# controller.net
KiCad netlist of a schematic drawn in Altium Designer
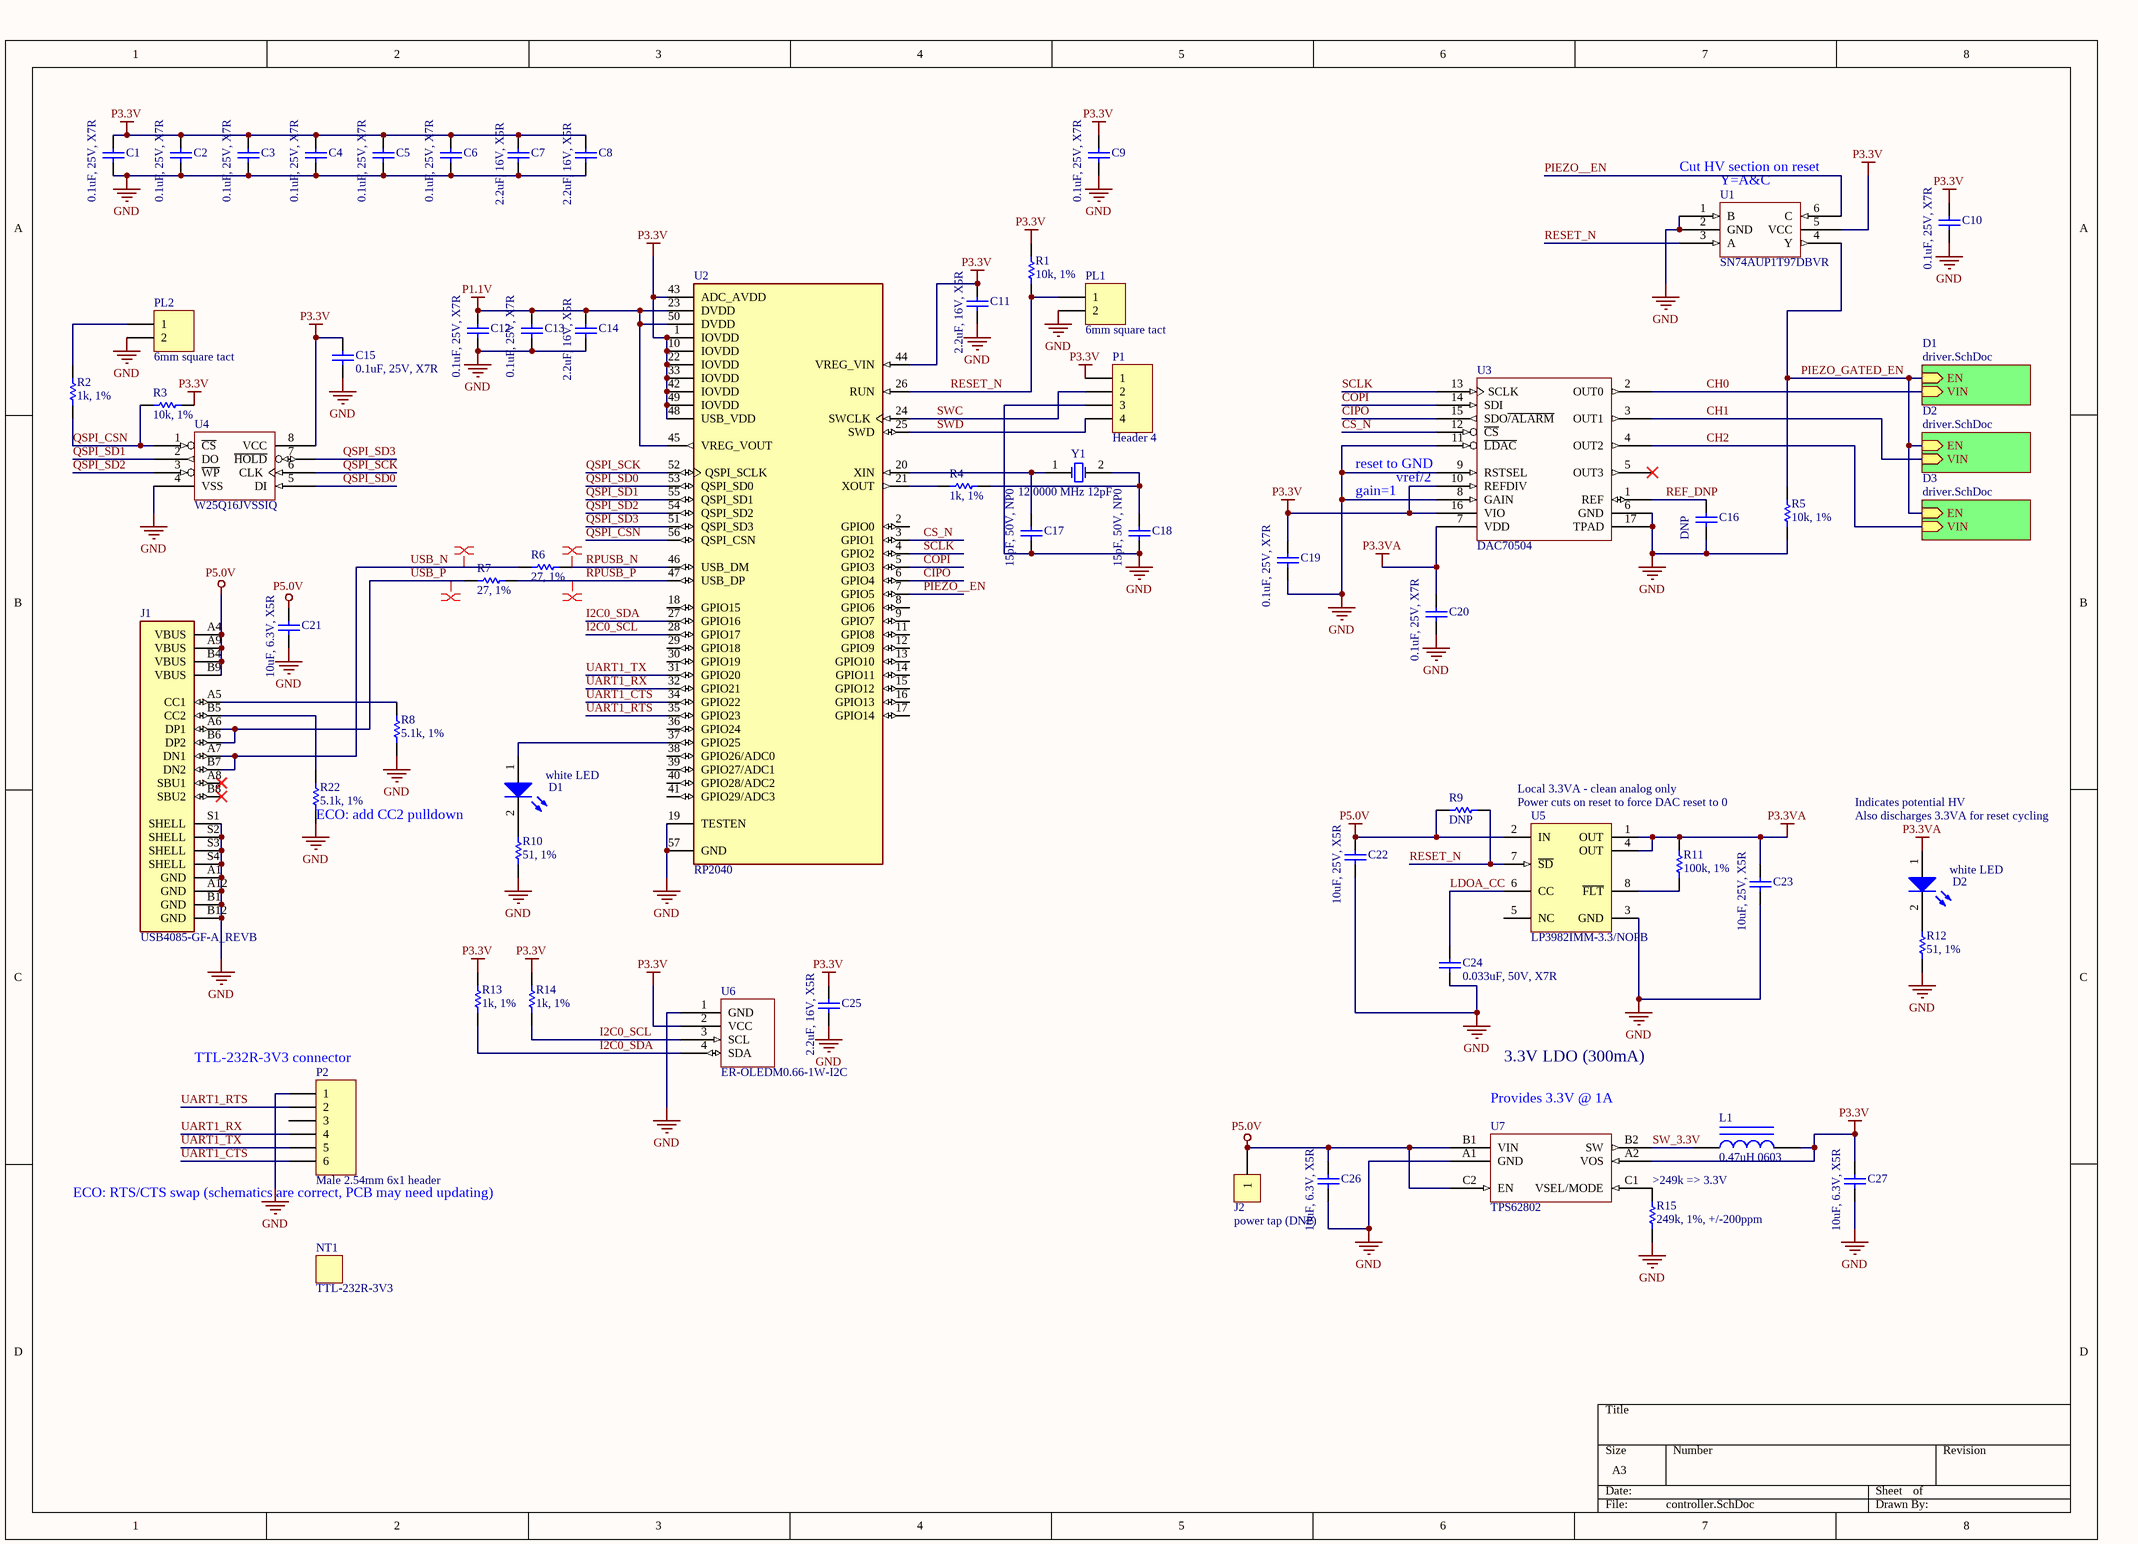
[diagram p0: controller.SchDoc]

(export (version "E")
  (design (tool "Eeschema 10.0.6"))
  (components
    (comp (ref "C1")
      (value "0.1uF, 25V, X7R")
      (footprint "B_CAP0603")
      (description "Capacitor (Semiconductor SIM Model)")
      (fields (field (name "MPN") "CC0603KRX7R8BB104"))
      (libsource (lib "Miscellaneous Devices") (part "Cap Semi"))
    )
    (comp (ref "C2")
      (value "0.1uF, 25V, X7R")
      (footprint "B_CAP0603")
      (description "Capacitor (Semiconductor SIM Model)")
      (fields (field (name "MPN") "CC0603KRX7R8BB104"))
      (libsource (lib "Miscellaneous Devices") (part "Cap Semi"))
    )
    (comp (ref "C3")
      (value "0.1uF, 25V, X7R")
      (footprint "B_CAP0603")
      (description "Capacitor (Semiconductor SIM Model)")
      (fields (field (name "MPN") "CC0603KRX7R8BB104"))
      (libsource (lib "Miscellaneous Devices") (part "Cap Semi"))
    )
    (comp (ref "C4")
      (value "0.1uF, 25V, X7R")
      (footprint "B_CAP0603")
      (description "Capacitor (Semiconductor SIM Model)")
      (fields (field (name "MPN") "CC0603KRX7R8BB104"))
      (libsource (lib "Miscellaneous Devices") (part "Cap Semi"))
    )
    (comp (ref "C5")
      (value "0.1uF, 25V, X7R")
      (footprint "B_CAP0603")
      (description "Capacitor (Semiconductor SIM Model)")
      (fields (field (name "MPN") "CC0603KRX7R8BB104"))
      (libsource (lib "Miscellaneous Devices") (part "Cap Semi"))
    )
    (comp (ref "C6")
      (value "0.1uF, 25V, X7R")
      (footprint "B_CAP0603")
      (description "Capacitor (Semiconductor SIM Model)")
      (fields (field (name "MPN") "CC0603KRX7R8BB104"))
      (libsource (lib "Miscellaneous Devices") (part "Cap Semi"))
    )
    (comp (ref "C7")
      (value "2.2uF, 16V, X5R")
      (footprint "B_CAP0603")
      (description "Capacitor (Semiconductor SIM Model)")
      (fields (field (name "MPN") "CL10A225KO8NNNC"))
      (libsource (lib "Miscellaneous Devices") (part "Cap Semi"))
    )
    (comp (ref "C8")
      (value "2.2uF, 16V, X5R")
      (footprint "B_CAP0603")
      (description "Capacitor (Semiconductor SIM Model)")
      (fields (field (name "MPN") "CL10A225KO8NNNC"))
      (libsource (lib "Miscellaneous Devices") (part "Cap Semi"))
    )
    (comp (ref "C9")
      (value "0.1uF, 25V, X7R")
      (footprint "B_CAP0603")
      (description "Capacitor (Semiconductor SIM Model)")
      (fields (field (name "MPN") "CC0603KRX7R8BB104"))
      (libsource (lib "Miscellaneous Devices") (part "Cap Semi"))
    )
    (comp (ref "C10")
      (value "0.1uF, 25V, X7R")
      (footprint "B_CAP0603")
      (description "Capacitor (Semiconductor SIM Model)")
      (fields (field (name "MPN") "CC0603KRX7R8BB104"))
      (libsource (lib "Miscellaneous Devices") (part "Cap Semi"))
    )
    (comp (ref "C11")
      (value "2.2uF, 16V, X5R")
      (footprint "B_CAP0603")
      (description "Capacitor (Semiconductor SIM Model)")
      (fields (field (name "MPN") "CL10A225KO8NNNC"))
      (libsource (lib "Miscellaneous Devices") (part "Cap Semi"))
    )
    (comp (ref "C12")
      (value "0.1uF, 25V, X7R")
      (footprint "B_CAP0603")
      (description "Capacitor (Semiconductor SIM Model)")
      (fields (field (name "MPN") "CC0603KRX7R8BB104"))
      (libsource (lib "Miscellaneous Devices") (part "Cap Semi"))
    )
    (comp (ref "C13")
      (value "0.1uF, 25V, X7R")
      (footprint "B_CAP0603")
      (description "Capacitor (Semiconductor SIM Model)")
      (fields (field (name "MPN") "CC0603KRX7R8BB104"))
      (libsource (lib "Miscellaneous Devices") (part "Cap Semi"))
    )
    (comp (ref "C14")
      (value "2.2uF, 16V, X5R")
      (footprint "B_CAP0603")
      (description "Capacitor (Semiconductor SIM Model)")
      (fields (field (name "MPN") "CL10A225KO8NNNC"))
      (libsource (lib "Miscellaneous Devices") (part "Cap Semi"))
    )
    (comp (ref "C15")
      (value "0.1uF, 25V, X7R")
      (footprint "B_CAP0603")
      (description "Capacitor (Semiconductor SIM Model)")
      (fields (field (name "MPN") "CC0603KRX7R8BB104"))
      (libsource (lib "Miscellaneous Devices") (part "Cap Semi"))
    )
    (comp (ref "C16")
      (value "DNP")
      (footprint "B_CAP0603")
      (description "Capacitor (Semiconductor SIM Model)")
      (libsource (lib "Miscellaneous Devices") (part "Cap Semi"))
    )
    (comp (ref "C17")
      (value "15pF, 50V, NP0")
      (footprint "B_CAP0603")
      (description "Capacitor (Semiconductor SIM Model)")
      (fields (field (name "MPN") "CL10C150JB81PNC"))
      (libsource (lib "Miscellaneous Devices") (part "Cap Semi"))
    )
    (comp (ref "C18")
      (value "15pF, 50V, NP0")
      (footprint "B_CAP0603")
      (description "Capacitor (Semiconductor SIM Model)")
      (fields (field (name "MPN") "CL10C150JB81PNC"))
      (libsource (lib "Miscellaneous Devices") (part "Cap Semi"))
    )
    (comp (ref "C19")
      (value "0.1uF, 25V, X7R")
      (footprint "B_CAP0603")
      (description "Capacitor (Semiconductor SIM Model)")
      (fields (field (name "MPN") "CC0603KRX7R8BB104"))
      (libsource (lib "Miscellaneous Devices") (part "Cap Semi"))
    )
    (comp (ref "C20")
      (value "0.1uF, 25V, X7R")
      (footprint "B_CAP0603")
      (description "Capacitor (Semiconductor SIM Model)")
      (fields (field (name "MPN") "CC0603KRX7R8BB104"))
      (libsource (lib "Miscellaneous Devices") (part "Cap Semi"))
    )
    (comp (ref "C21")
      (value "10uF, 6.3V, X5R")
      (footprint "B_CAP0603")
      (description "Capacitor (Semiconductor SIM Model)")
      (fields (field (name "MPN") "CL10A106MQ8NNNC"))
      (libsource (lib "Miscellaneous Devices") (part "Cap Semi"))
    )
    (comp (ref "C22")
      (value "10uF, 25V, X5R")
      (footprint "B_CAP0805")
      (description "Capacitor (Semiconductor SIM Model)")
      (fields (field (name "MPN") "GRM21BR61E106KA73L"))
      (libsource (lib "Miscellaneous Devices") (part "Cap Semi"))
    )
    (comp (ref "C23")
      (value "10uF, 25V, X5R")
      (footprint "B_CAP0805")
      (description "Capacitor (Semiconductor SIM Model)")
      (fields (field (name "MPN") "GRM21BR61E106KA73L"))
      (libsource (lib "Miscellaneous Devices") (part "Cap Semi"))
    )
    (comp (ref "C24")
      (value "0.033uF, 50V, X7R")
      (footprint "B_CAP0603")
      (description "Capacitor (Semiconductor SIM Model)")
      (fields (field (name "MPN") "CL10B333KB8NNNC"))
      (libsource (lib "Miscellaneous Devices") (part "Cap Semi"))
    )
    (comp (ref "C25")
      (value "2.2uF, 16V, X5R")
      (footprint "B_CAP0603")
      (description "Capacitor (Semiconductor SIM Model)")
      (fields (field (name "MPN") "CL10A225KO8NNNC"))
      (libsource (lib "Miscellaneous Devices") (part "Cap Semi"))
    )
    (comp (ref "C26")
      (value "10uF, 6.3V, X5R")
      (footprint "B_CAP0603")
      (description "Capacitor (Semiconductor SIM Model)")
      (fields (field (name "MPN") "CL10A106MQ8NNNC"))
      (libsource (lib "Miscellaneous Devices") (part "Cap Semi"))
    )
    (comp (ref "C27")
      (value "10uF, 6.3V, X5R")
      (footprint "B_CAP0603")
      (description "Capacitor (Semiconductor SIM Model)")
      (fields (field (name "MPN") "CL10A106MQ8NNNC"))
      (libsource (lib "Miscellaneous Devices") (part "Cap Semi"))
    )
    (comp (ref "D1")
      (value "white LED")
      (footprint "B_LED0805")
      (description "Typical RED, GREEN, YELLOW, AMBER GaAs LED")
      (fields (field (name "MPN") "EAST2012WA1"))
      (libsource (lib "Miscellaneous Devices") (part "LED2"))
    )
    (comp (ref "D2")
      (value "white LED")
      (footprint "B_LED0805")
      (description "Typical RED, GREEN, YELLOW, AMBER GaAs LED")
      (fields (field (name "MPN") "EAST2012WA1"))
      (libsource (lib "Miscellaneous Devices") (part "LED2"))
    )
    (comp (ref "J1")
      (value "USB4085-GF-A_REVB")
      (footprint "GCT_USB4085-GF-A_REVB")
      (fields (field (name "MF") "Global Connector Technology") (field (name "MP") "USB4085-GF-A"))
      (libsource (lib "USB4085-GF-A_REVB") (part "USB4085-GF-A_REVB"))
    )
    (comp (ref "J2")
      (value "power tap (DNP)")
      (footprint "RESTAP-0603")
      (description "Connector")
      (fields (field (name "MPN") "DNP"))
      (libsource (lib "*") (part "CON1"))
    )
    (comp (ref "L1")
      (value "0.47uH 0603")
      (footprint "B_IND0603")
      (description "Magnetic-Core Inductor")
      (fields (field (name "MPN") "TFM160808ALC-R47MTAA"))
      (libsource (lib "Miscellaneous Devices") (part "Inductor Iron"))
    )
    (comp (ref "NT1")
      (value "TTL-232R-3V3")
      (description "Placeholder for non-board BOM items")
      (libsource (lib "commonsch") (part "NOTE"))
    )
    (comp (ref "P1")
      (value "Header 4")
      (footprint "HDR1X4")
      (description "Header, 4-Pin")
      (fields (field (name "MPN") "PH1-04-UA / ANY") (field (name "PUBLISHER") "Altium Limited"))
      (libsource (lib "Miscellaneous Connectors") (part "Header 4"))
    )
    (comp (ref "P2")
      (value "Male 2.54mm 6x1 header")
      (footprint "HDR1X6")
      (description "Header, 6-Pin")
      (fields (field (name "MPN") "PH1-06-UA / ANY") (field (name "PUBLISHER") "Altium Limited"))
      (libsource (lib "Miscellaneous Connectors") (part "Header 6"))
    )
    (comp (ref "PL1")
      (value "6mm square tact")
      (footprint "PANASONIC_EVPAS")
      (description "Header, 2-Pin")
      (fields (field (name "MPN") "EVP-ASAC1A") (field (name "PUBLISHER") "Altium Limited"))
      (libsource (lib "Miscellaneous Connectors") (part "Header 2"))
    )
    (comp (ref "PL2")
      (value "6mm square tact")
      (footprint "PANASONIC_EVPAS")
      (description "Header, 2-Pin")
      (fields (field (name "MPN") "EVP-ASAC1A") (field (name "PUBLISHER") "Altium Limited"))
      (libsource (lib "Miscellaneous Connectors") (part "Header 2"))
    )
    (comp (ref "R1")
      (value "10k, 1%")
      (footprint "B_RES0603")
      (description "Resistor")
      (fields (field (name "MPN") "RC0603FR-0710KL"))
      (libsource (lib "Miscellaneous Devices") (part "Res1"))
    )
    (comp (ref "R2")
      (value "1k, 1%")
      (footprint "B_RES0603")
      (description "Resistor")
      (fields (field (name "MPN") "ANY"))
      (libsource (lib "Miscellaneous Devices") (part "Res1"))
    )
    (comp (ref "R3")
      (value "10k, 1%")
      (footprint "B_RES0603")
      (description "Resistor")
      (fields (field (name "MPN") "RC0603FR-0710KL"))
      (libsource (lib "Miscellaneous Devices") (part "Res1"))
    )
    (comp (ref "R4")
      (value "1k, 1%")
      (footprint "B_RES0603")
      (description "Resistor")
      (fields (field (name "MPN") "ANY"))
      (libsource (lib "Miscellaneous Devices") (part "Res1"))
    )
    (comp (ref "R5")
      (value "10k, 1%")
      (footprint "B_RES0603")
      (description "Resistor")
      (fields (field (name "MPN") "RC0603FR-0710KL"))
      (libsource (lib "Miscellaneous Devices") (part "Res1"))
    )
    (comp (ref "R6")
      (value "27, 1%")
      (footprint "B_RES0603")
      (description "Resistor")
      (fields (field (name "MPN") "ANY"))
      (libsource (lib "Miscellaneous Devices") (part "Res1"))
    )
    (comp (ref "R7")
      (value "27, 1%")
      (footprint "B_RES0603")
      (description "Resistor")
      (fields (field (name "MPN") "ANY"))
      (libsource (lib "Miscellaneous Devices") (part "Res1"))
    )
    (comp (ref "R8")
      (value "5.1k, 1%")
      (footprint "B_RES0603")
      (description "Resistor")
      (fields (field (name "MPN") "RC0603FR-075K1L"))
      (libsource (lib "Miscellaneous Devices") (part "Res1"))
    )
    (comp (ref "R9")
      (value "DNP")
      (footprint "B_RES0603")
      (description "Resistor")
      (libsource (lib "Miscellaneous Devices") (part "Res1"))
    )
    (comp (ref "R10")
      (value "51, 1%")
      (footprint "B_RES0603")
      (description "Resistor")
      (fields (field (name "MPN") "ANY"))
      (libsource (lib "Miscellaneous Devices") (part "Res1"))
    )
    (comp (ref "R11")
      (value "100k, 1%")
      (footprint "B_RES0603")
      (description "Resistor")
      (fields (field (name "MPN") "RC0603FR-07100KL"))
      (libsource (lib "Miscellaneous Devices") (part "Res1"))
    )
    (comp (ref "R12")
      (value "51, 1%")
      (footprint "B_RES0603")
      (description "Resistor")
      (fields (field (name "MPN") "ANY"))
      (libsource (lib "Miscellaneous Devices") (part "Res1"))
    )
    (comp (ref "R13")
      (value "1k, 1%")
      (footprint "B_RES0603")
      (description "Resistor")
      (fields (field (name "MPN") "ANY"))
      (libsource (lib "Miscellaneous Devices") (part "Res1"))
    )
    (comp (ref "R14")
      (value "1k, 1%")
      (footprint "B_RES0603")
      (description "Resistor")
      (fields (field (name "MPN") "ANY"))
      (libsource (lib "Miscellaneous Devices") (part "Res1"))
    )
    (comp (ref "R15")
      (value "249k, 1%, +/-200ppm")
      (footprint "B_RES0402")
      (description "Resistor")
      (fields (field (name "MPN") "RC0402FR-07249KL"))
      (libsource (lib "Miscellaneous Devices") (part "Res1"))
    )
    (comp (ref "R22")
      (value "5.1k, 1%")
      (footprint "B_RES0603")
      (description "Resistor")
      (fields (field (name "MPN") "RC0603FR-075K1L"))
      (libsource (lib "Miscellaneous Devices") (part "Res1"))
    )
    (comp (ref "U1")
      (value "SN74AUP1T97DBVR")
      (footprint "SOT26A-6N")
      (description "Low power configurable gate with voltage translator")
      (libsource (lib "commonsch-new") (part "74AUP1T97L6X"))
    )
    (comp (ref "U2")
      (value "RP2040")
      (footprint "QFN40P700X700X90-57N")
      (description "RP2040 chip for Raspberry Pi Pico - ARMÂ® CortexÂ®-M0+ MCU 32-Bit")
      (fields (field (name "MF") "Raspberry Pi") (field (name "MPN") "SC0914(7/13)"))
      (libsource (lib "RP2040") (part "RP2040"))
    )
    (comp (ref "U3")
      (value "DAC70504")
      (footprint "QFN50P300X300X80_HS-17N")
      (description "Quad SPI DAC with internal reference, in 16- (8), 14- (7), and 12-(6) bit variants")
      (fields (field (name "MPN") "DAC70504RTET"))
      (libsource (lib "commonsch-new") (part "DACx0504"))
    )
    (comp (ref "U4")
      (value "W25Q16JVSSIQ")
      (footprint "SOIC127P790X216-8N")
      (description "16Mbit SPI NOR FLASH")
      (libsource (lib "commonsch") (part "EN25P05-50GCP"))
    )
    (comp (ref "U5")
      (value "LP3982IMM-3.3/NOPB")
      (footprint "MUA08A_N")
      (description "Micropower, Ultra Low-Dropout, Low-Noise, 300mA CMOS Regulator, 8-pin Mini SOIC, Pb-Free")
      (fields (field (name "MANUFACTURER") "National Semiconductor"))
      (libsource (lib "National Semiconductor LDO") (part "LP3982IMM-3.3/NOPB"))
    )
    (comp (ref "U6")
      (value "ER-OLEDM0.66-1W-I2C")
      (footprint "ER-OLEDM0.66-1W-I2C")
      (description "0.66\" white OLED module, I2C")
      (libsource (lib "commonsch-new") (part "ER-OLEDM0.66-1W-I2C"))
    )
    (comp (ref "U7")
      (value "TPS62802")
      (footprint "BGA6C35P2X3_70X105X40_NSMD")
      (description "Buck regulator, 4MHz, 0.6A, 1.8V-3.3V, low Iq")
      (fields (field (name "MPN") "TPS62802YKAR"))
      (libsource (lib "altium-import") (part "root_0_TPS62802_"))
    )
    (comp (ref "Y1")
      (value "12.0000 MHz 12pF")
      (footprint "NDK_NX5032A")
      (description "Crystal Oscillator")
      (fields (field (name "MPN") "ECS-120-12-30-JGN-TR") (field (name "PUBLISHER") "Altium Limited"))
      (libsource (lib "Miscellaneous Devices") (part "XTAL"))
    )
  )
  (nets
    (net (code "1") (name "/CH0") (class "Default")
      (node (ref "U3") (pin "2") (pinfunction "OUT0_2") (pintype "output"))
    )
    (net (code "2") (name "/CH1") (class "Default")
      (node (ref "U3") (pin "3") (pinfunction "OUT1_3") (pintype "output"))
    )
    (net (code "3") (name "/CH2") (class "Default")
      (node (ref "U3") (pin "4") (pinfunction "OUT2_4") (pintype "output"))
    )
    (net (code "4") (name "/CIPO") (class "Default")
      (node (ref "U2") (pin "6") (pinfunction "GPIO4_6") (pintype "bidirectional"))
      (node (ref "U3") (pin "15") (pinfunction "SDO~{/ALARM}_15") (pintype "output"))
    )
    (net (code "5") (name "/COPI") (class "Default")
      (node (ref "U2") (pin "5") (pinfunction "GPIO3_5") (pintype "bidirectional"))
      (node (ref "U3") (pin "14") (pinfunction "SDI_14") (pintype "input"))
    )
    (net (code "6") (name "/CS_N") (class "Default")
      (node (ref "U2") (pin "3") (pinfunction "GPIO1_3") (pintype "bidirectional"))
      (node (ref "U3") (pin "12") (pinfunction "~{CS}_12") (pintype "input"))
    )
    (net (code "7") (name "/I2C0_SCL") (class "Default")
      (node (ref "R14") (pin "1") (pinfunction "1_1") (pintype "passive"))
      (node (ref "U2") (pin "28") (pinfunction "GPIO17_28") (pintype "bidirectional"))
      (node (ref "U6") (pin "3") (pinfunction "SCL_3") (pintype "input"))
    )
    (net (code "8") (name "/I2C0_SDA") (class "Default")
      (node (ref "R13") (pin "1") (pinfunction "1_1") (pintype "passive"))
      (node (ref "U2") (pin "27") (pinfunction "GPIO16_27") (pintype "bidirectional"))
      (node (ref "U6") (pin "4") (pinfunction "SDA_4") (pintype "bidirectional"))
    )
    (net (code "9") (name "/LDOA_CC") (class "Default")
      (node (ref "C24") (pin "2") (pinfunction "2_2") (pintype "passive"))
      (node (ref "U5") (pin "6") (pinfunction "CC_6") (pintype "passive"))
    )
    (net (code "10") (name "/PIEZO_GATED_EN") (class "Default")
      (node (ref "R5") (pin "1") (pinfunction "1_1") (pintype "passive"))
      (node (ref "U1") (pin "4") (pinfunction "Y_4") (pintype "output"))
    )
    (net (code "11") (name "/PIEZO__EN") (class "Default")
      (node (ref "U1") (pin "6") (pinfunction "C_6") (pintype "input"))
      (node (ref "U2") (pin "7") (pinfunction "GPIO5_7") (pintype "bidirectional"))
    )
    (net (code "12") (name "/QSPI_CSN") (class "Default")
      (node (ref "R2") (pin "1") (pinfunction "1_1") (pintype "passive"))
      (node (ref "R3") (pin "1") (pinfunction "1_1") (pintype "passive"))
      (node (ref "U2") (pin "56") (pinfunction "QSPI_CSN_56") (pintype "bidirectional"))
      (node (ref "U4") (pin "1") (pinfunction "~{CS}_1") (pintype "input"))
    )
    (net (code "13") (name "/QSPI_SCK") (class "Default")
      (node (ref "U2") (pin "52") (pinfunction "QSPI_SCLK_52") (pintype "bidirectional"))
      (node (ref "U4") (pin "6") (pinfunction "CLK_6") (pintype "input"))
    )
    (net (code "14") (name "/QSPI_SD0") (class "Default")
      (node (ref "U2") (pin "53") (pinfunction "QSPI_SD0_53") (pintype "bidirectional"))
      (node (ref "U4") (pin "5") (pinfunction "DI_5") (pintype "input"))
    )
    (net (code "15") (name "/QSPI_SD1") (class "Default")
      (node (ref "U2") (pin "55") (pinfunction "QSPI_SD1_55") (pintype "bidirectional"))
      (node (ref "U4") (pin "2") (pinfunction "DO_2") (pintype "output"))
    )
    (net (code "16") (name "/QSPI_SD2") (class "Default")
      (node (ref "U2") (pin "54") (pinfunction "QSPI_SD2_54") (pintype "bidirectional"))
      (node (ref "U4") (pin "3") (pinfunction "~{WP}_3") (pintype "input"))
    )
    (net (code "17") (name "/QSPI_SD3") (class "Default")
      (node (ref "U2") (pin "51") (pinfunction "QSPI_SD3_51") (pintype "bidirectional"))
      (node (ref "U4") (pin "7") (pinfunction "~{HOLD}_7") (pintype "bidirectional"))
    )
    (net (code "18") (name "/REF_DNP") (class "Default")
      (node (ref "C16") (pin "1") (pinfunction "1_1") (pintype "passive"))
      (node (ref "U3") (pin "1") (pinfunction "REF_1") (pintype "bidirectional"))
    )
    (net (code "19") (name "/RESET_N") (class "Default")
      (node (ref "PL1") (pin "1") (pinfunction "1_1") (pintype "passive"))
      (node (ref "R1") (pin "2") (pinfunction "2_2") (pintype "passive"))
      (node (ref "R9") (pin "2") (pinfunction "2_2") (pintype "passive"))
      (node (ref "U1") (pin "3") (pinfunction "A_3") (pintype "input"))
      (node (ref "U2") (pin "26") (pinfunction "RUN_26") (pintype "input"))
      (node (ref "U5") (pin "7") (pinfunction "~{SD}_7") (pintype "input"))
    )
    (net (code "20") (name "/RPUSB_N") (class "Default")
      (node (ref "R6") (pin "2") (pinfunction "2_2") (pintype "passive"))
      (node (ref "U2") (pin "46") (pinfunction "USB_DM_46") (pintype "bidirectional"))
    )
    (net (code "21") (name "/RPUSB_P") (class "Default")
      (node (ref "R7") (pin "2") (pinfunction "2_2") (pintype "passive"))
      (node (ref "U2") (pin "47") (pinfunction "USB_DP_47") (pintype "bidirectional"))
    )
    (net (code "22") (name "/SCLK") (class "Default")
      (node (ref "U2") (pin "4") (pinfunction "GPIO2_4") (pintype "bidirectional"))
      (node (ref "U3") (pin "13") (pinfunction "SCLK_13") (pintype "input"))
    )
    (net (code "23") (name "/SWC") (class "Default")
      (node (ref "P1") (pin "2") (pinfunction "2_2") (pintype "passive"))
      (node (ref "U2") (pin "24") (pinfunction "SWCLK_24") (pintype "input"))
    )
    (net (code "24") (name "/SWD") (class "Default")
      (node (ref "P1") (pin "4") (pinfunction "4_4") (pintype "passive"))
      (node (ref "U2") (pin "25") (pinfunction "SWD_25") (pintype "bidirectional"))
    )
    (net (code "25") (name "/SW_3.3V") (class "Default")
      (node (ref "L1") (pin "1") (pinfunction "1_1") (pintype "passive"))
      (node (ref "U7") (pin "B2") (pinfunction "SW_B2") (pintype "output"))
    )
    (net (code "26") (name "/UART1_CTS") (class "Default")
      (node (ref "P2") (pin "6") (pinfunction "6_6") (pintype "passive"))
      (node (ref "U2") (pin "34") (pinfunction "GPIO22_34") (pintype "bidirectional"))
    )
    (net (code "27") (name "/UART1_RTS") (class "Default")
      (node (ref "P2") (pin "2") (pinfunction "2_2") (pintype "passive"))
      (node (ref "U2") (pin "35") (pinfunction "GPIO23_35") (pintype "bidirectional"))
    )
    (net (code "28") (name "/UART1_RX") (class "Default")
      (node (ref "P2") (pin "4") (pinfunction "4_4") (pintype "passive"))
      (node (ref "U2") (pin "32") (pinfunction "GPIO21_32") (pintype "bidirectional"))
    )
    (net (code "29") (name "/UART1_TX") (class "Default")
      (node (ref "P2") (pin "5") (pinfunction "5_5") (pintype "passive"))
      (node (ref "U2") (pin "31") (pinfunction "GPIO20_31") (pintype "bidirectional"))
    )
    (net (code "30") (name "/USB_N") (class "Default")
      (node (ref "J1") (pin "A7") (pinfunction "DN1_A7") (pintype "bidirectional"))
      (node (ref "J1") (pin "B7") (pinfunction "DN2_B7") (pintype "bidirectional"))
      (node (ref "R6") (pin "1") (pinfunction "1_1") (pintype "passive"))
    )
    (net (code "31") (name "/USB_P") (class "Default")
      (node (ref "J1") (pin "A6") (pinfunction "DP1_A6") (pintype "bidirectional"))
      (node (ref "J1") (pin "B6") (pinfunction "DP2_B6") (pintype "bidirectional"))
      (node (ref "R7") (pin "1") (pinfunction "1_1") (pintype "passive"))
    )
    (net (code "32") (name "GND") (class "Default")
      (node (ref "C1") (pin "2") (pinfunction "2_2") (pintype "passive"))
      (node (ref "C10") (pin "2") (pinfunction "2_2") (pintype "passive"))
      (node (ref "C11") (pin "2") (pinfunction "2_2") (pintype "passive"))
      (node (ref "C12") (pin "2") (pinfunction "2_2") (pintype "passive"))
      (node (ref "C13") (pin "2") (pinfunction "2_2") (pintype "passive"))
      (node (ref "C14") (pin "2") (pinfunction "2_2") (pintype "passive"))
      (node (ref "C15") (pin "1") (pinfunction "1_1") (pintype "passive"))
      (node (ref "C16") (pin "2") (pinfunction "2_2") (pintype "passive"))
      (node (ref "C17") (pin "1") (pinfunction "1_1") (pintype "passive"))
      (node (ref "C18") (pin "1") (pinfunction "1_1") (pintype "passive"))
      (node (ref "C19") (pin "2") (pinfunction "2_2") (pintype "passive"))
      (node (ref "C2") (pin "2") (pinfunction "2_2") (pintype "passive"))
      (node (ref "C20") (pin "2") (pinfunction "2_2") (pintype "passive"))
      (node (ref "C21") (pin "2") (pinfunction "2_2") (pintype "passive"))
      (node (ref "C22") (pin "2") (pinfunction "2_2") (pintype "passive"))
      (node (ref "C23") (pin "2") (pinfunction "2_2") (pintype "passive"))
      (node (ref "C24") (pin "1") (pinfunction "1_1") (pintype "passive"))
      (node (ref "C25") (pin "2") (pinfunction "2_2") (pintype "passive"))
      (node (ref "C26") (pin "2") (pinfunction "2_2") (pintype "passive"))
      (node (ref "C27") (pin "2") (pinfunction "2_2") (pintype "passive"))
      (node (ref "C3") (pin "2") (pinfunction "2_2") (pintype "passive"))
      (node (ref "C4") (pin "2") (pinfunction "2_2") (pintype "passive"))
      (node (ref "C5") (pin "2") (pinfunction "2_2") (pintype "passive"))
      (node (ref "C6") (pin "2") (pinfunction "2_2") (pintype "passive"))
      (node (ref "C7") (pin "2") (pinfunction "2_2") (pintype "passive"))
      (node (ref "C8") (pin "2") (pinfunction "2_2") (pintype "passive"))
      (node (ref "C9") (pin "2") (pinfunction "2_2") (pintype "passive"))
      (node (ref "J1") (pin "A1") (pinfunction "GND_A1") (pintype "power_in"))
      (node (ref "J1") (pin "A12") (pinfunction "GND_A12") (pintype "power_in"))
      (node (ref "J1") (pin "B1") (pinfunction "GND_B1") (pintype "power_in"))
      (node (ref "J1") (pin "B12") (pinfunction "GND_B12") (pintype "power_in"))
      (node (ref "J1") (pin "S1") (pinfunction "SHELL_S1") (pintype "passive"))
      (node (ref "J1") (pin "S2") (pinfunction "SHELL_S2") (pintype "passive"))
      (node (ref "J1") (pin "S3") (pinfunction "SHELL_S3") (pintype "passive"))
      (node (ref "J1") (pin "S4") (pinfunction "SHELL_S4") (pintype "passive"))
      (node (ref "P1") (pin "3") (pinfunction "3_3") (pintype "passive"))
      (node (ref "P2") (pin "1") (pinfunction "1_1") (pintype "passive"))
      (node (ref "PL1") (pin "2") (pinfunction "2_2") (pintype "passive"))
      (node (ref "PL2") (pin "2") (pinfunction "2_2") (pintype "passive"))
      (node (ref "R10") (pin "1") (pinfunction "1_1") (pintype "passive"))
      (node (ref "R12") (pin "1") (pinfunction "1_1") (pintype "passive"))
      (node (ref "R15") (pin "2") (pinfunction "2_2") (pintype "passive"))
      (node (ref "R22") (pin "1") (pinfunction "1_1") (pintype "passive"))
      (node (ref "R5") (pin "2") (pinfunction "2_2") (pintype "passive"))
      (node (ref "R8") (pin "1") (pinfunction "1_1") (pintype "passive"))
      (node (ref "U1") (pin "1") (pinfunction "B_1") (pintype "input"))
      (node (ref "U1") (pin "2") (pinfunction "GND_2") (pintype "power_in"))
      (node (ref "U2") (pin "19") (pinfunction "TESTEN_19") (pintype "passive"))
      (node (ref "U2") (pin "57") (pinfunction "GND_57") (pintype "power_in"))
      (node (ref "U3") (pin "11") (pinfunction "~{LDAC}_11") (pintype "input"))
      (node (ref "U3") (pin "17") (pinfunction "TPAD_17") (pintype "power_in"))
      (node (ref "U3") (pin "6") (pinfunction "GND_6") (pintype "power_in"))
      (node (ref "U3") (pin "8") (pinfunction "GAIN_8") (pintype "input"))
      (node (ref "U3") (pin "9") (pinfunction "RSTSEL_9") (pintype "input"))
      (node (ref "U4") (pin "4") (pinfunction "VSS_4") (pintype "power_in"))
      (node (ref "U5") (pin "3") (pinfunction "GND_3") (pintype "power_in"))
      (node (ref "U6") (pin "1") (pinfunction "GND_1") (pintype "power_in"))
      (node (ref "U7") (pin "A1") (pinfunction "GND_A1") (pintype "power_in"))
    )
    (net (code "33") (name "Net-(D1-A)") (class "Default")
      (node (ref "D1") (pin "1") (pinfunction "A_1") (pintype "passive"))
      (node (ref "U2") (pin "37") (pinfunction "GPIO25_37") (pintype "bidirectional"))
    )
    (net (code "34") (name "Net-(D1-K)") (class "Default")
      (node (ref "D1") (pin "2") (pinfunction "K_2") (pintype "passive"))
      (node (ref "R10") (pin "2") (pinfunction "2_2") (pintype "passive"))
    )
    (net (code "35") (name "Net-(D2-K)") (class "Default")
      (node (ref "D2") (pin "2") (pinfunction "K_2") (pintype "passive"))
      (node (ref "R12") (pin "2") (pinfunction "2_2") (pintype "passive"))
    )
    (net (code "36") (name "Net-(J1-CC1)") (class "Default")
      (node (ref "J1") (pin "A5") (pinfunction "CC1_A5") (pintype "bidirectional"))
      (node (ref "R8") (pin "2") (pinfunction "2_2") (pintype "passive"))
    )
    (net (code "37") (name "Net-(J1-CC2)") (class "Default")
      (node (ref "J1") (pin "B5") (pinfunction "CC2_B5") (pintype "bidirectional"))
      (node (ref "R22") (pin "2") (pinfunction "2_2") (pintype "passive"))
    )
    (net (code "38") (name "Net-(PL2-Pad1)") (class "Default")
      (node (ref "PL2") (pin "1") (pinfunction "1_1") (pintype "passive"))
      (node (ref "R2") (pin "2") (pinfunction "2_2") (pintype "passive"))
    )
    (net (code "39") (name "Net-(U2-XIN)") (class "Default")
      (node (ref "C17") (pin "2") (pinfunction "2_2") (pintype "passive"))
      (node (ref "U2") (pin "20") (pinfunction "XIN_20") (pintype "input"))
      (node (ref "Y1") (pin "1") (pinfunction "OSC1_1") (pintype "passive"))
    )
    (net (code "40") (name "Net-(U2-XOUT)") (class "Default")
      (node (ref "R4") (pin "1") (pinfunction "1_1") (pintype "passive"))
      (node (ref "U2") (pin "21") (pinfunction "XOUT_21") (pintype "output"))
    )
    (net (code "41") (name "Net-(U5-~{FLT})") (class "Default")
      (node (ref "R11") (pin "1") (pinfunction "1_1") (pintype "passive"))
      (node (ref "U5") (pin "8") (pinfunction "~{FLT}_8") (pintype "open_collector"))
    )
    (net (code "42") (name "Net-(U7-VSEL{slash}MODE)") (class "Default")
      (node (ref "R15") (pin "1") (pinfunction "1_1") (pintype "passive"))
      (node (ref "U7") (pin "C1") (pinfunction "VSEL/MODE_C1") (pintype "input"))
    )
    (net (code "43") (name "Net-(Y1-OSC2)") (class "Default")
      (node (ref "C18") (pin "2") (pinfunction "2_2") (pintype "passive"))
      (node (ref "R4") (pin "2") (pinfunction "2_2") (pintype "passive"))
      (node (ref "Y1") (pin "2") (pinfunction "OSC2_2") (pintype "passive"))
    )
    (net (code "44") (name "P1.1V") (class "Default")
      (node (ref "C12") (pin "1") (pinfunction "1_1") (pintype "passive"))
      (node (ref "C13") (pin "1") (pinfunction "1_1") (pintype "passive"))
      (node (ref "C14") (pin "1") (pinfunction "1_1") (pintype "passive"))
      (node (ref "U2") (pin "23") (pinfunction "DVDD_23") (pintype "power_in"))
      (node (ref "U2") (pin "45") (pinfunction "VREG_VOUT_45") (pintype "output"))
      (node (ref "U2") (pin "50") (pinfunction "DVDD_50") (pintype "power_in"))
    )
    (net (code "45") (name "P3.3V") (class "Default")
      (node (ref "C1") (pin "1") (pinfunction "1_1") (pintype "passive"))
      (node (ref "C10") (pin "1") (pinfunction "1_1") (pintype "passive"))
      (node (ref "C11") (pin "1") (pinfunction "1_1") (pintype "passive"))
      (node (ref "C15") (pin "2") (pinfunction "2_2") (pintype "passive"))
      (node (ref "C19") (pin "1") (pinfunction "1_1") (pintype "passive"))
      (node (ref "C2") (pin "1") (pinfunction "1_1") (pintype "passive"))
      (node (ref "C25") (pin "1") (pinfunction "1_1") (pintype "passive"))
      (node (ref "C27") (pin "1") (pinfunction "1_1") (pintype "passive"))
      (node (ref "C3") (pin "1") (pinfunction "1_1") (pintype "passive"))
      (node (ref "C4") (pin "1") (pinfunction "1_1") (pintype "passive"))
      (node (ref "C5") (pin "1") (pinfunction "1_1") (pintype "passive"))
      (node (ref "C6") (pin "1") (pinfunction "1_1") (pintype "passive"))
      (node (ref "C7") (pin "1") (pinfunction "1_1") (pintype "passive"))
      (node (ref "C8") (pin "1") (pinfunction "1_1") (pintype "passive"))
      (node (ref "C9") (pin "1") (pinfunction "1_1") (pintype "passive"))
      (node (ref "L1") (pin "2") (pinfunction "2_2") (pintype "passive"))
      (node (ref "P1") (pin "1") (pinfunction "1_1") (pintype "passive"))
      (node (ref "R1") (pin "1") (pinfunction "1_1") (pintype "passive"))
      (node (ref "R13") (pin "2") (pinfunction "2_2") (pintype "passive"))
      (node (ref "R14") (pin "2") (pinfunction "2_2") (pintype "passive"))
      (node (ref "R3") (pin "2") (pinfunction "2_2") (pintype "passive"))
      (node (ref "U1") (pin "5") (pinfunction "VCC_5") (pintype "power_in"))
      (node (ref "U2") (pin "1") (pinfunction "IOVDD_1") (pintype "power_in"))
      (node (ref "U2") (pin "10") (pinfunction "IOVDD_10") (pintype "power_in"))
      (node (ref "U2") (pin "22") (pinfunction "IOVDD_22") (pintype "power_in"))
      (node (ref "U2") (pin "33") (pinfunction "IOVDD_33") (pintype "power_in"))
      (node (ref "U2") (pin "42") (pinfunction "IOVDD_42") (pintype "power_in"))
      (node (ref "U2") (pin "43") (pinfunction "ADC_AVDD_43") (pintype "power_in"))
      (node (ref "U2") (pin "44") (pinfunction "VREG_VIN_44") (pintype "input"))
      (node (ref "U2") (pin "48") (pinfunction "USB_VDD_48") (pintype "power_in"))
      (node (ref "U2") (pin "49") (pinfunction "IOVDD_49") (pintype "power_in"))
      (node (ref "U3") (pin "10") (pinfunction "REFDIV_10") (pintype "input"))
      (node (ref "U3") (pin "16") (pinfunction "VIO_16") (pintype "power_in"))
      (node (ref "U4") (pin "8") (pinfunction "VCC_8") (pintype "power_in"))
      (node (ref "U6") (pin "2") (pinfunction "VCC_2") (pintype "power_in"))
      (node (ref "U7") (pin "A2") (pinfunction "VOS_A2") (pintype "input"))
    )
    (net (code "46") (name "P3.3VA") (class "Default")
      (node (ref "C20") (pin "1") (pinfunction "1_1") (pintype "passive"))
      (node (ref "C23") (pin "1") (pinfunction "1_1") (pintype "passive"))
      (node (ref "D2") (pin "1") (pinfunction "A_1") (pintype "passive"))
      (node (ref "R11") (pin "2") (pinfunction "2_2") (pintype "passive"))
      (node (ref "U3") (pin "7") (pinfunction "VDD_7") (pintype "power_in"))
      (node (ref "U5") (pin "1") (pinfunction "OUT_1") (pintype "power_in"))
      (node (ref "U5") (pin "4") (pinfunction "OUT_4") (pintype "power_in"))
    )
    (net (code "47") (name "P5.0V") (class "Default")
      (node (ref "C21") (pin "1") (pinfunction "1_1") (pintype "passive"))
      (node (ref "C22") (pin "1") (pinfunction "1_1") (pintype "passive"))
      (node (ref "C26") (pin "1") (pinfunction "1_1") (pintype "passive"))
      (node (ref "J1") (pin "A4") (pinfunction "VBUS_A4") (pintype "power_in"))
      (node (ref "J1") (pin "A9") (pinfunction "VBUS_A9") (pintype "power_in"))
      (node (ref "J1") (pin "B4") (pinfunction "VBUS_B4") (pintype "power_in"))
      (node (ref "J1") (pin "B9") (pinfunction "VBUS_B9") (pintype "power_in"))
      (node (ref "J2") (pin "1") (pinfunction "1_1") (pintype "passive"))
      (node (ref "R9") (pin "1") (pinfunction "1_1") (pintype "passive"))
      (node (ref "U5") (pin "2") (pinfunction "IN_2") (pintype "power_in"))
      (node (ref "U7") (pin "B1") (pinfunction "VIN_B1") (pintype "power_in"))
      (node (ref "U7") (pin "C2") (pinfunction "EN_C2") (pintype "input"))
    )
    (net (code "48") (name "unconnected-(J1-SBU1-PadA8)") (class "Default")
      (node (ref "J1") (pin "A8") (pinfunction "SBU1_A8") (pintype "bidirectional+no_connect"))
    )
    (net (code "49") (name "unconnected-(J1-SBU2-PadB8)") (class "Default")
      (node (ref "J1") (pin "B8") (pinfunction "SBU2_B8") (pintype "bidirectional+no_connect"))
    )
    (net (code "50") (name "unconnected-(P2-Pad3)") (class "Default")
      (node (ref "P2") (pin "3") (pinfunction "3_3") (pintype "passive"))
    )
    (net (code "51") (name "unconnected-(U2-GPIO0-Pad2)") (class "Default")
      (node (ref "U2") (pin "2") (pinfunction "GPIO0_2") (pintype "bidirectional"))
    )
    (net (code "52") (name "unconnected-(U2-GPIO6-Pad8)") (class "Default")
      (node (ref "U2") (pin "8") (pinfunction "GPIO6_8") (pintype "bidirectional"))
    )
    (net (code "53") (name "unconnected-(U2-GPIO7-Pad9)") (class "Default")
      (node (ref "U2") (pin "9") (pinfunction "GPIO7_9") (pintype "bidirectional"))
    )
    (net (code "54") (name "unconnected-(U2-GPIO8-Pad11)") (class "Default")
      (node (ref "U2") (pin "11") (pinfunction "GPIO8_11") (pintype "bidirectional"))
    )
    (net (code "55") (name "unconnected-(U2-GPIO9-Pad12)") (class "Default")
      (node (ref "U2") (pin "12") (pinfunction "GPIO9_12") (pintype "bidirectional"))
    )
    (net (code "56") (name "unconnected-(U2-GPIO10-Pad13)") (class "Default")
      (node (ref "U2") (pin "13") (pinfunction "GPIO10_13") (pintype "bidirectional"))
    )
    (net (code "57") (name "unconnected-(U2-GPIO11-Pad14)") (class "Default")
      (node (ref "U2") (pin "14") (pinfunction "GPIO11_14") (pintype "bidirectional"))
    )
    (net (code "58") (name "unconnected-(U2-GPIO12-Pad15)") (class "Default")
      (node (ref "U2") (pin "15") (pinfunction "GPIO12_15") (pintype "bidirectional"))
    )
    (net (code "59") (name "unconnected-(U2-GPIO13-Pad16)") (class "Default")
      (node (ref "U2") (pin "16") (pinfunction "GPIO13_16") (pintype "bidirectional"))
    )
    (net (code "60") (name "unconnected-(U2-GPIO14-Pad17)") (class "Default")
      (node (ref "U2") (pin "17") (pinfunction "GPIO14_17") (pintype "bidirectional"))
    )
    (net (code "61") (name "unconnected-(U2-GPIO15-Pad18)") (class "Default")
      (node (ref "U2") (pin "18") (pinfunction "GPIO15_18") (pintype "bidirectional"))
    )
    (net (code "62") (name "unconnected-(U2-GPIO18-Pad29)") (class "Default")
      (node (ref "U2") (pin "29") (pinfunction "GPIO18_29") (pintype "bidirectional"))
    )
    (net (code "63") (name "unconnected-(U2-GPIO19-Pad30)") (class "Default")
      (node (ref "U2") (pin "30") (pinfunction "GPIO19_30") (pintype "bidirectional"))
    )
    (net (code "64") (name "unconnected-(U2-GPIO24-Pad36)") (class "Default")
      (node (ref "U2") (pin "36") (pinfunction "GPIO24_36") (pintype "bidirectional"))
    )
    (net (code "65") (name "unconnected-(U2-GPIO26{slash}ADC0-Pad38)") (class "Default")
      (node (ref "U2") (pin "38") (pinfunction "GPIO26/ADC0_38") (pintype "bidirectional"))
    )
    (net (code "66") (name "unconnected-(U2-GPIO27{slash}ADC1-Pad39)") (class "Default")
      (node (ref "U2") (pin "39") (pinfunction "GPIO27/ADC1_39") (pintype "bidirectional"))
    )
    (net (code "67") (name "unconnected-(U2-GPIO28{slash}ADC2-Pad40)") (class "Default")
      (node (ref "U2") (pin "40") (pinfunction "GPIO28/ADC2_40") (pintype "bidirectional"))
    )
    (net (code "68") (name "unconnected-(U2-GPIO29{slash}ADC3-Pad41)") (class "Default")
      (node (ref "U2") (pin "41") (pinfunction "GPIO29/ADC3_41") (pintype "bidirectional"))
    )
    (net (code "69") (name "unconnected-(U3-OUT3-Pad5)") (class "Default")
      (node (ref "U3") (pin "5") (pinfunction "OUT3_5") (pintype "output+no_connect"))
    )
    (net (code "70") (name "unconnected-(U5-NC-Pad5)") (class "Default")
      (node (ref "U5") (pin "5") (pinfunction "NC_5") (pintype "passive"))
    )
  )
)
